# CRD.net
KiCad netlist of a schematic drawn in EAGLE
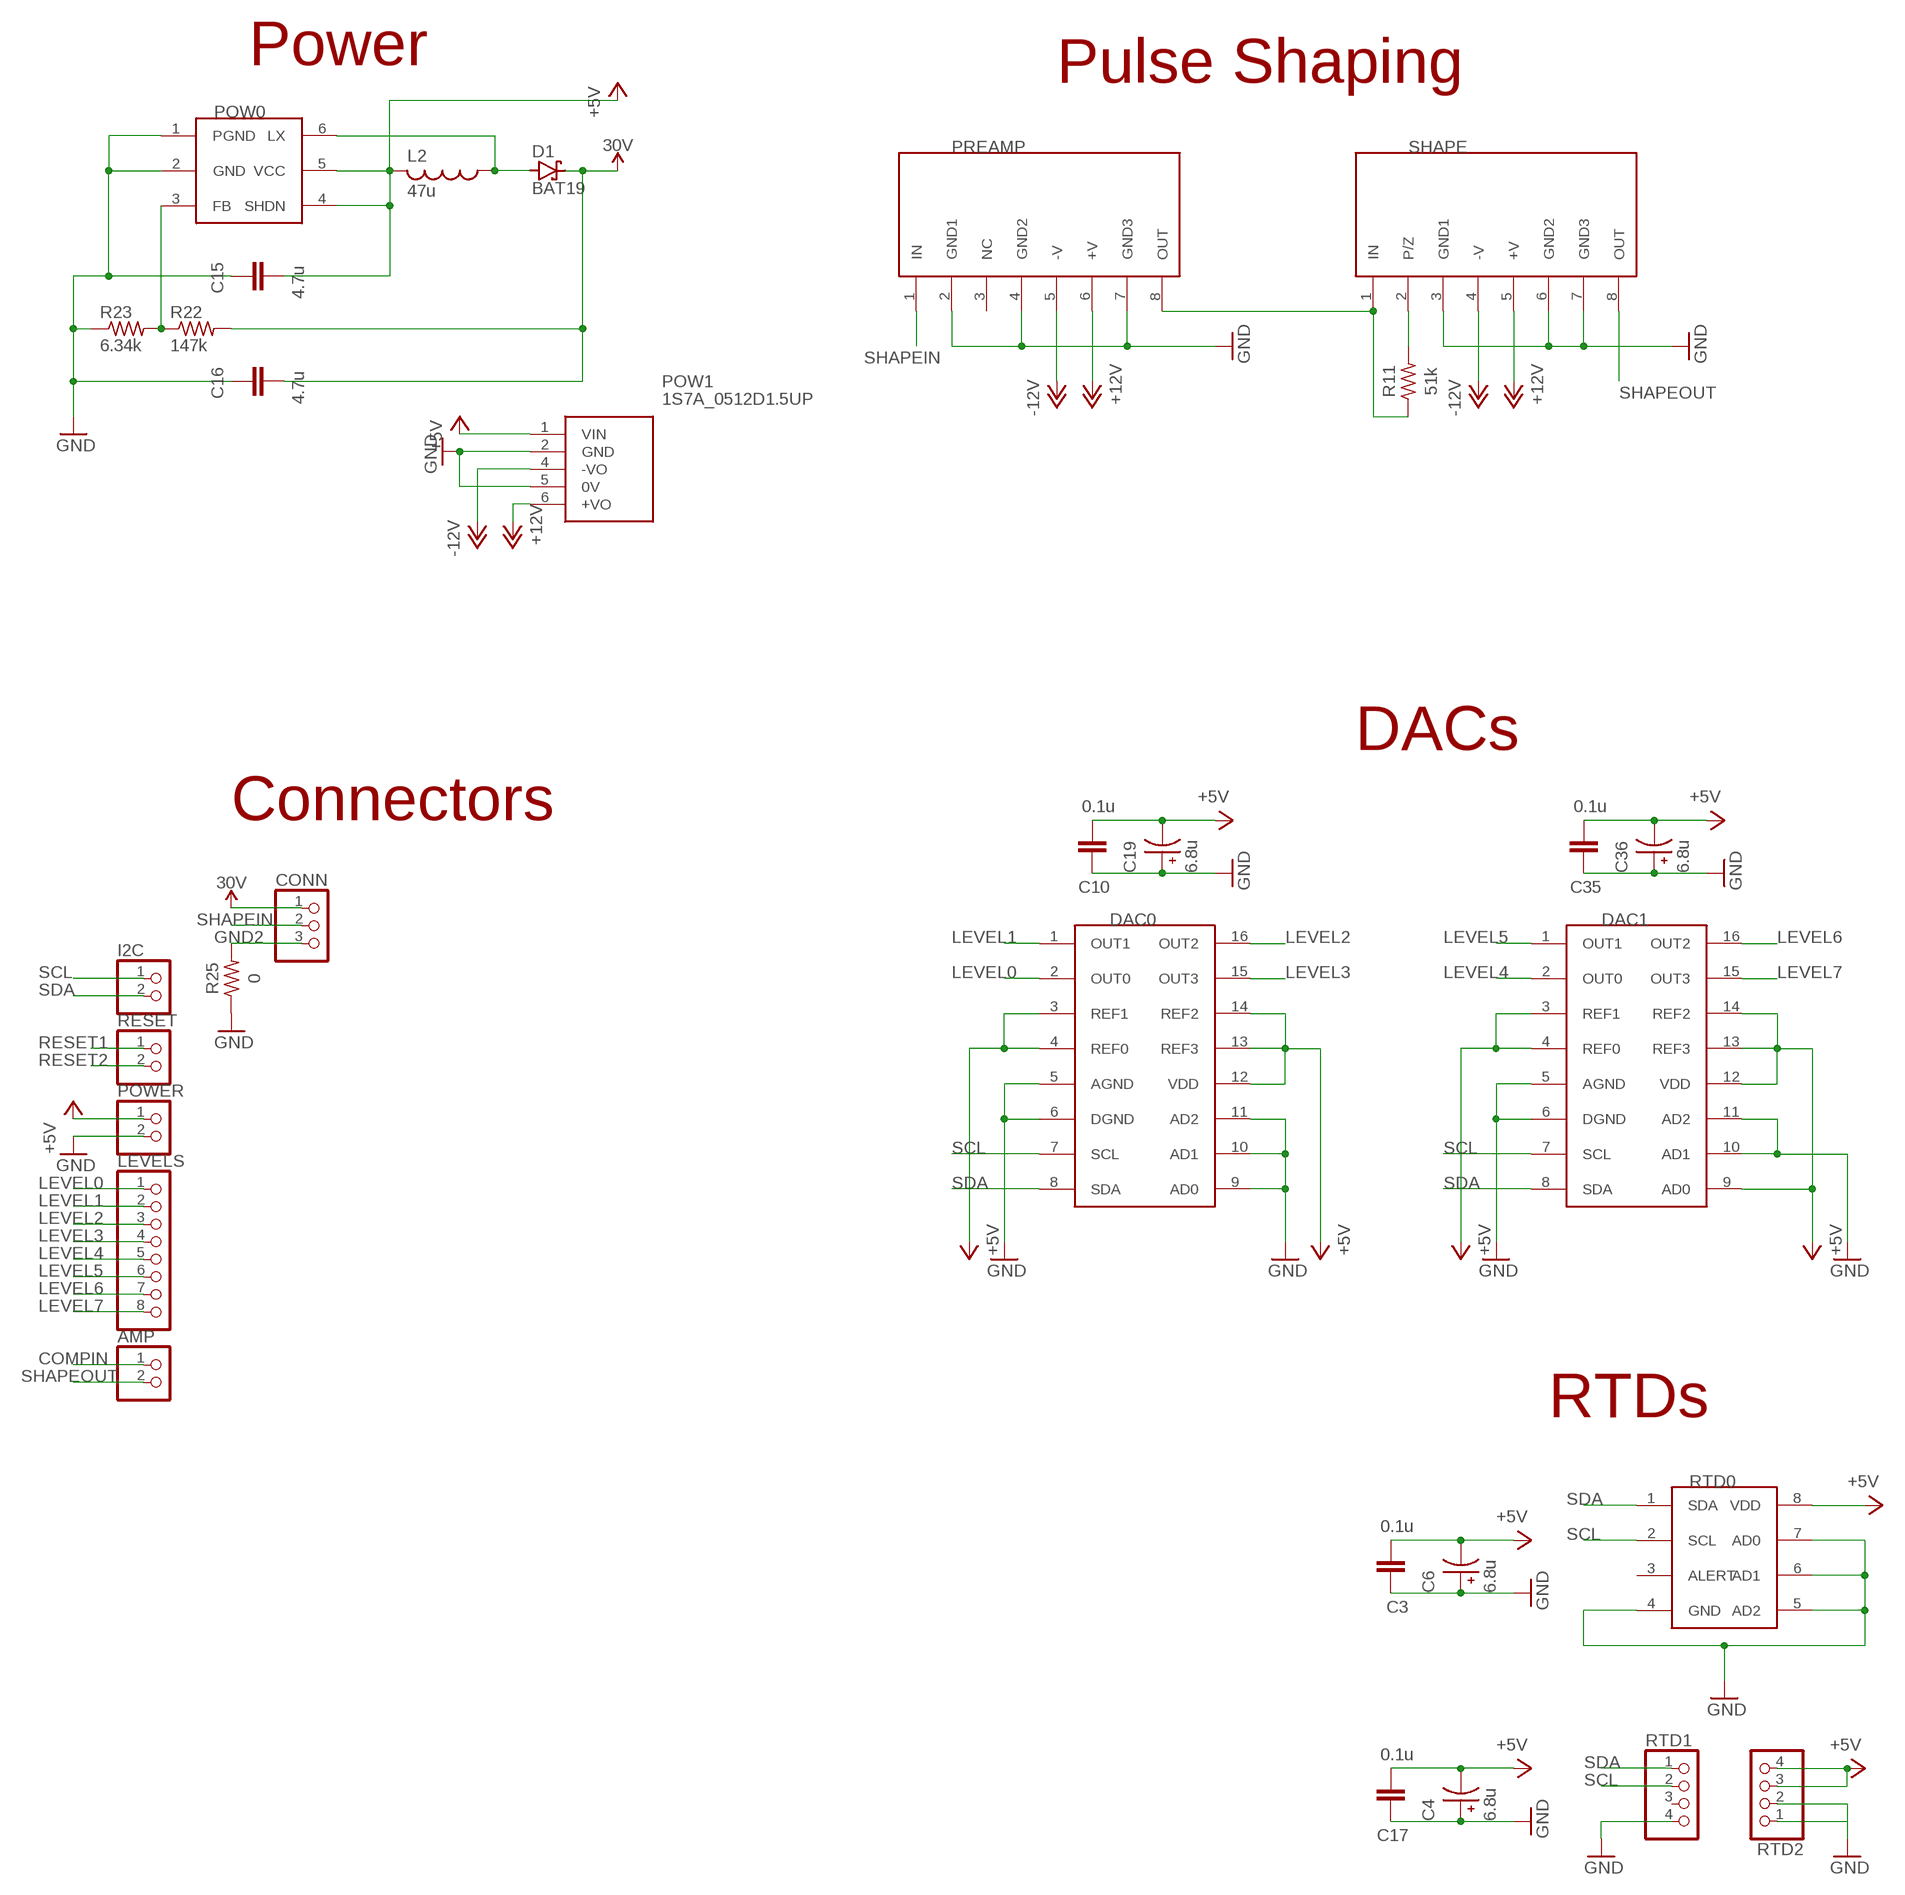
[diagram p0: schematic, sheet 1, part 1 of 2]
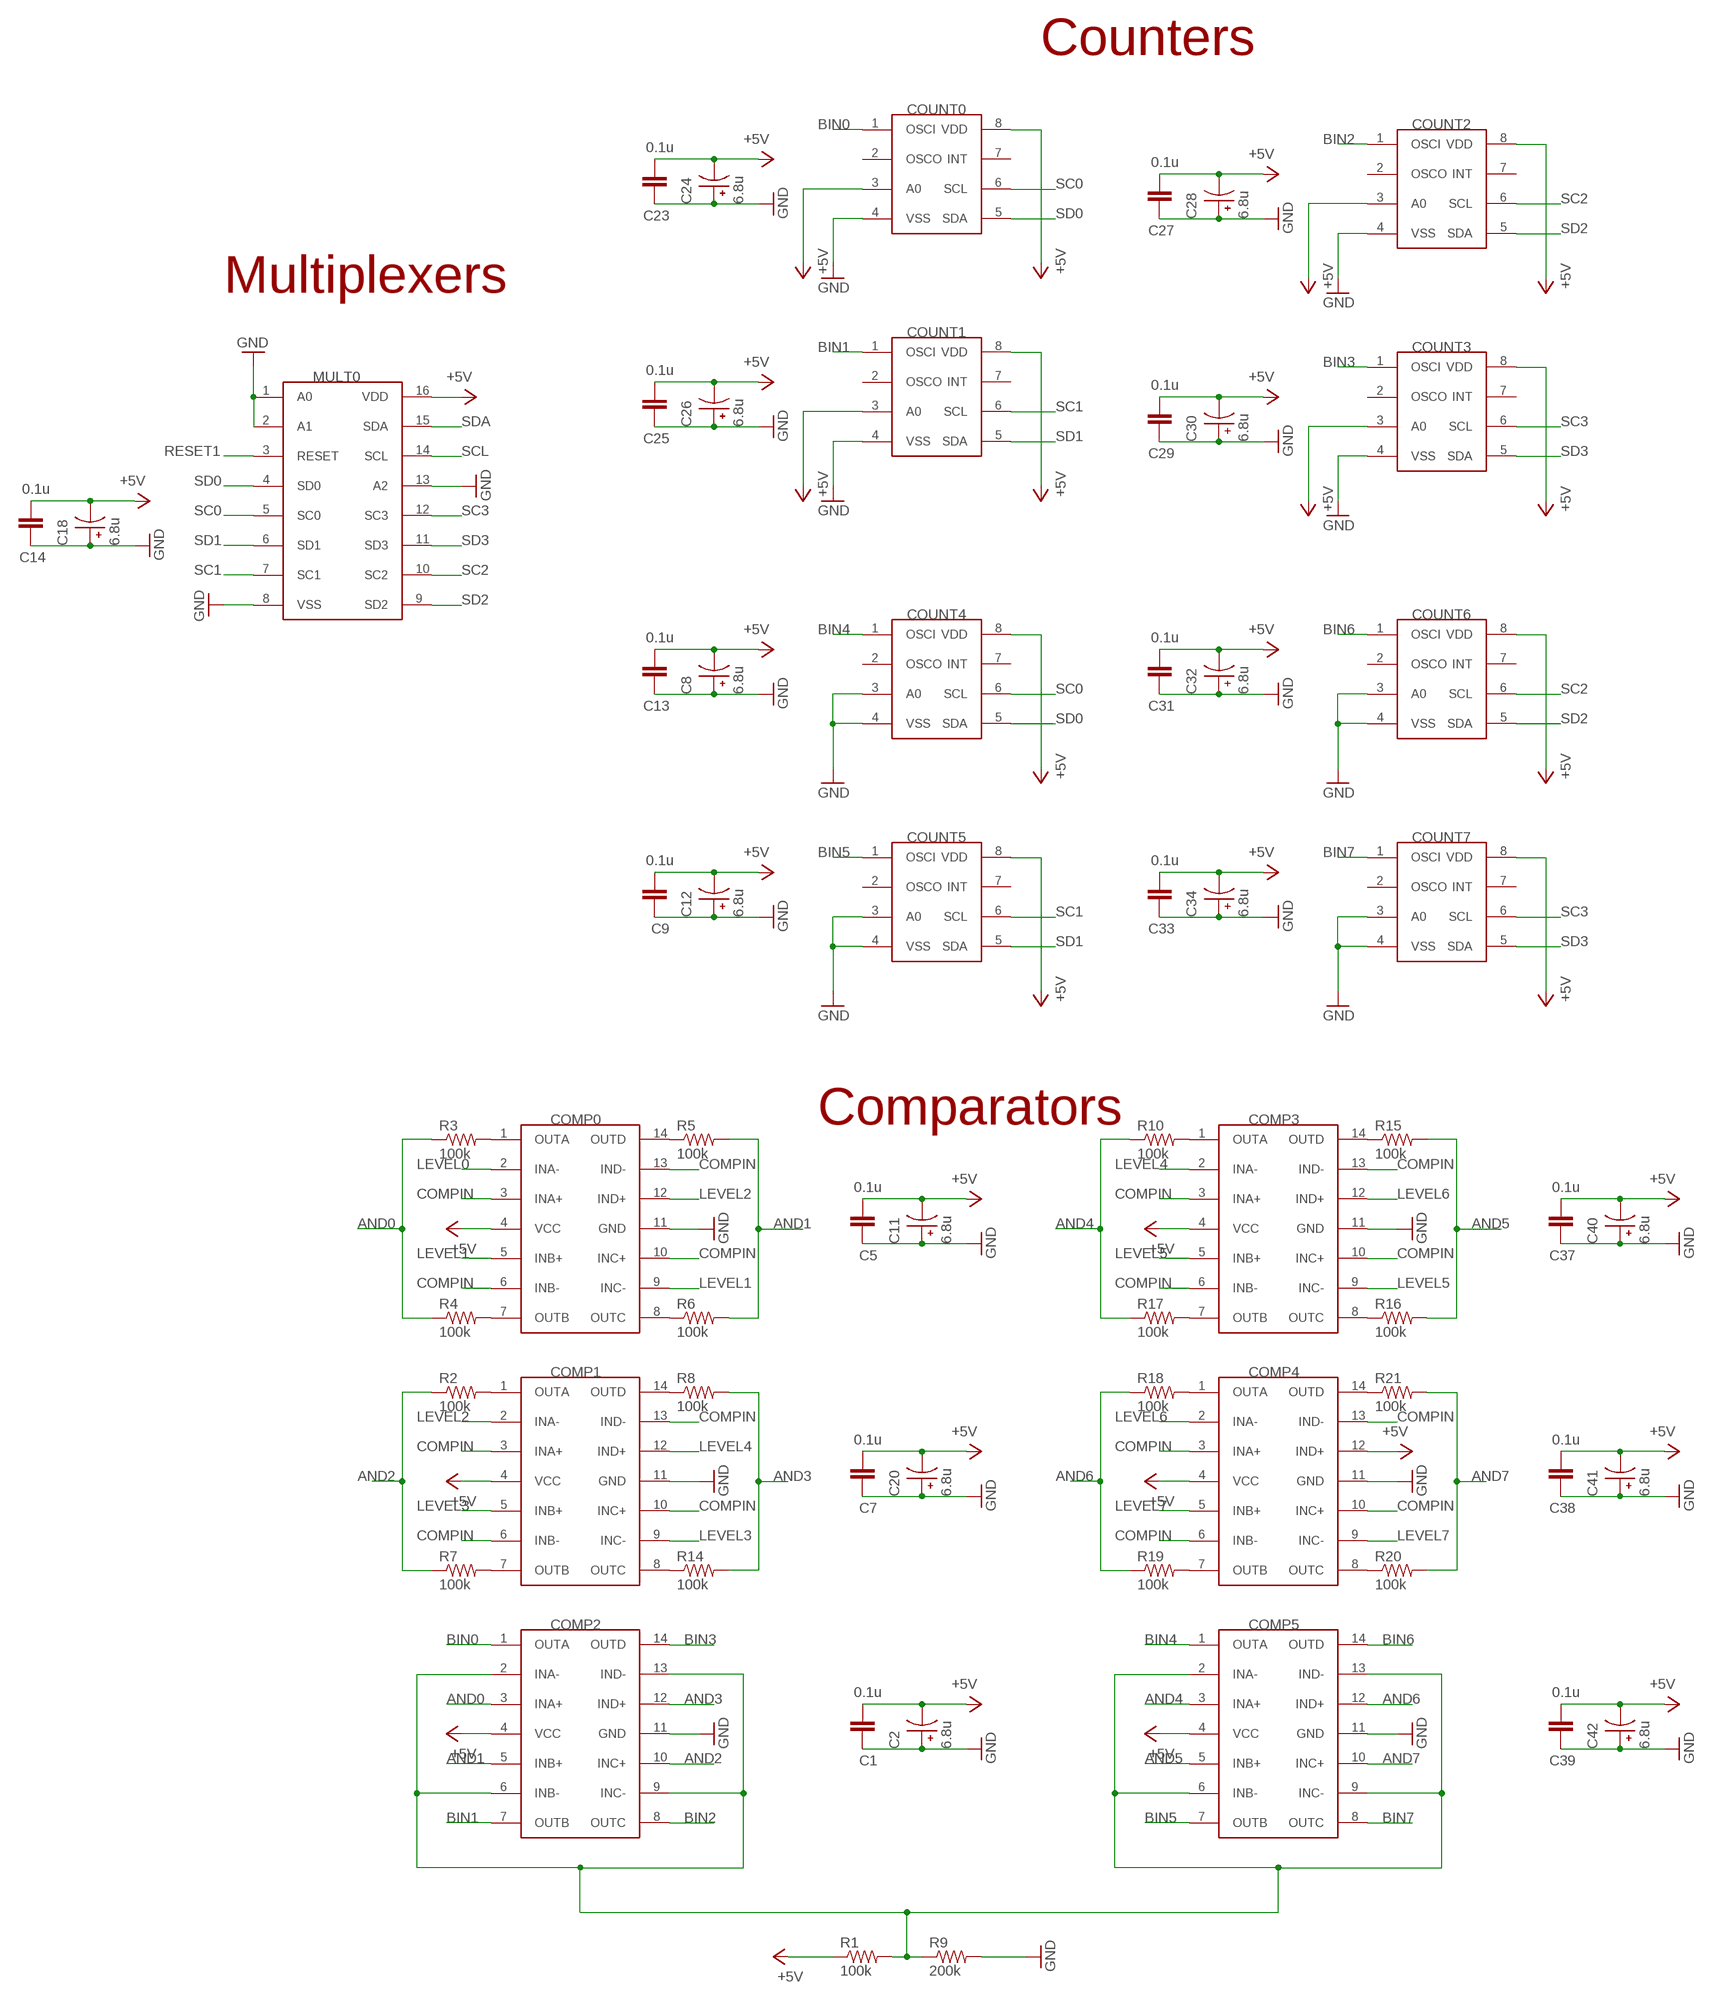
[diagram p1: schematic, sheet 1, part 2 of 2]

(export (version "E")
  (design (tool "Eeschema 10.0.6"))
  (components
    (comp (ref "AMP")
      (value "PINHD-1X2")
      (footprint "eagle-import:1X02")
      (libsource (lib "eagle-import") (part "PINHD-1X2"))
    )
    (comp (ref "C1")
      (value "0.1u")
      (footprint "eagle-import:CAP_1206")
      (fields
        (field (name "DIGIKEY_PART_NUMBER") "GRM31CR60J107ME39L")
        (field (name "MANUFACTURER") "Murata Electronics North America")
        (field (name "CREATED_BY") "PCBLayout.com")
      )
      (libsource (lib "eagle-import") (part "GRM31CR60J107ME39L"))
    )
    (comp (ref "C2")
      (value "6.8u")
      (footprint "eagle-import:CAPPRD150W45D400H700")
      (fields
        (field (name "DIGI-KEY_PART_NUMBER") "P14493-ND")
        (field (name "MF") "Panasonic")
        (field (name "MP") "EEAGA1V6R8")
      )
      (libsource (lib "eagle-import") (part "EEAGA1V6R8"))
    )
    (comp (ref "C3")
      (value "0.1u")
      (footprint "eagle-import:CAP_1206")
      (fields
        (field (name "DIGIKEY_PART_NUMBER") "GRM31CR60J107ME39L")
        (field (name "MANUFACTURER") "Murata Electronics North America")
        (field (name "CREATED_BY") "PCBLayout.com")
      )
      (libsource (lib "eagle-import") (part "GRM31CR60J107ME39L"))
    )
    (comp (ref "C4")
      (value "6.8u")
      (footprint "eagle-import:CAPPRD150W45D400H700")
      (fields
        (field (name "DIGI-KEY_PART_NUMBER") "P14493-ND")
        (field (name "MF") "Panasonic")
        (field (name "MP") "EEAGA1V6R8")
      )
      (libsource (lib "eagle-import") (part "EEAGA1V6R8"))
    )
    (comp (ref "C5")
      (value "0.1u")
      (footprint "eagle-import:CAP_1206")
      (fields
        (field (name "DIGIKEY_PART_NUMBER") "GRM31CR60J107ME39L")
        (field (name "MANUFACTURER") "Murata Electronics North America")
        (field (name "CREATED_BY") "PCBLayout.com")
      )
      (libsource (lib "eagle-import") (part "GRM31CR60J107ME39L"))
    )
    (comp (ref "C6")
      (value "6.8u")
      (footprint "eagle-import:CAPPRD150W45D400H700")
      (fields
        (field (name "DIGI-KEY_PART_NUMBER") "P14493-ND")
        (field (name "MF") "Panasonic")
        (field (name "MP") "EEAGA1V6R8")
      )
      (libsource (lib "eagle-import") (part "EEAGA1V6R8"))
    )
    (comp (ref "C7")
      (value "0.1u")
      (footprint "eagle-import:CAP_1206")
      (fields
        (field (name "DIGIKEY_PART_NUMBER") "GRM31CR60J107ME39L")
        (field (name "MANUFACTURER") "Murata Electronics North America")
        (field (name "CREATED_BY") "PCBLayout.com")
      )
      (libsource (lib "eagle-import") (part "GRM31CR60J107ME39L"))
    )
    (comp (ref "C8")
      (value "6.8u")
      (footprint "eagle-import:CAPPRD150W45D400H700")
      (fields
        (field (name "DIGI-KEY_PART_NUMBER") "P14493-ND")
        (field (name "MF") "Panasonic")
        (field (name "MP") "EEAGA1V6R8")
      )
      (libsource (lib "eagle-import") (part "EEAGA1V6R8"))
    )
    (comp (ref "C9")
      (value "0.1u")
      (footprint "eagle-import:CAP_1206")
      (fields
        (field (name "DIGIKEY_PART_NUMBER") "GRM31CR60J107ME39L")
        (field (name "MANUFACTURER") "Murata Electronics North America")
        (field (name "CREATED_BY") "PCBLayout.com")
      )
      (libsource (lib "eagle-import") (part "GRM31CR60J107ME39L"))
    )
    (comp (ref "C10")
      (value "0.1u")
      (footprint "eagle-import:CAP_1206")
      (fields
        (field (name "DIGIKEY_PART_NUMBER") "GRM31CR60J107ME39L")
        (field (name "MANUFACTURER") "Murata Electronics North America")
        (field (name "CREATED_BY") "PCBLayout.com")
      )
      (libsource (lib "eagle-import") (part "GRM31CR60J107ME39L"))
    )
    (comp (ref "C11")
      (value "6.8u")
      (footprint "eagle-import:CAPPRD150W45D400H700")
      (fields
        (field (name "DIGI-KEY_PART_NUMBER") "P14493-ND")
        (field (name "MF") "Panasonic")
        (field (name "MP") "EEAGA1V6R8")
      )
      (libsource (lib "eagle-import") (part "EEAGA1V6R8"))
    )
    (comp (ref "C12")
      (value "6.8u")
      (footprint "eagle-import:CAPPRD150W45D400H700")
      (fields
        (field (name "DIGI-KEY_PART_NUMBER") "P14493-ND")
        (field (name "MF") "Panasonic")
        (field (name "MP") "EEAGA1V6R8")
      )
      (libsource (lib "eagle-import") (part "EEAGA1V6R8"))
    )
    (comp (ref "C13")
      (value "0.1u")
      (footprint "eagle-import:CAP_1206")
      (fields
        (field (name "DIGIKEY_PART_NUMBER") "GRM31CR60J107ME39L")
        (field (name "MANUFACTURER") "Murata Electronics North America")
        (field (name "CREATED_BY") "PCBLayout.com")
      )
      (libsource (lib "eagle-import") (part "GRM31CR60J107ME39L"))
    )
    (comp (ref "C14")
      (value "0.1u")
      (footprint "eagle-import:CAP_1206")
      (fields
        (field (name "DIGIKEY_PART_NUMBER") "GRM31CR60J107ME39L")
        (field (name "MANUFACTURER") "Murata Electronics North America")
        (field (name "CREATED_BY") "PCBLayout.com")
      )
      (libsource (lib "eagle-import") (part "GRM31CR60J107ME39L"))
    )
    (comp (ref "C15")
      (value "4.7u")
      (footprint "eagle-import:CAP_1206")
      (fields
        (field (name "DIGIKEY_PART_NUMBER") "GRM31CR60J107ME39L")
        (field (name "MANUFACTURER") "Murata Electronics North America")
        (field (name "CREATED_BY") "PCBLayout.com")
      )
      (libsource (lib "eagle-import") (part "GRM31CR60J107ME39L"))
    )
    (comp (ref "C16")
      (value "4.7u")
      (footprint "eagle-import:CAP_1206")
      (fields
        (field (name "DIGIKEY_PART_NUMBER") "GRM31CR60J107ME39L")
        (field (name "MANUFACTURER") "Murata Electronics North America")
        (field (name "CREATED_BY") "PCBLayout.com")
      )
      (libsource (lib "eagle-import") (part "GRM31CR60J107ME39L"))
    )
    (comp (ref "C17")
      (value "0.1u")
      (footprint "eagle-import:CAP_1206")
      (fields
        (field (name "DIGIKEY_PART_NUMBER") "GRM31CR60J107ME39L")
        (field (name "MANUFACTURER") "Murata Electronics North America")
        (field (name "CREATED_BY") "PCBLayout.com")
      )
      (libsource (lib "eagle-import") (part "GRM31CR60J107ME39L"))
    )
    (comp (ref "C18")
      (value "6.8u")
      (footprint "eagle-import:CAPPRD150W45D400H700")
      (fields
        (field (name "DIGI-KEY_PART_NUMBER") "P14493-ND")
        (field (name "MF") "Panasonic")
        (field (name "MP") "EEAGA1V6R8")
      )
      (libsource (lib "eagle-import") (part "EEAGA1V6R8"))
    )
    (comp (ref "C19")
      (value "6.8u")
      (footprint "eagle-import:CAPPRD150W45D400H700")
      (fields
        (field (name "DIGI-KEY_PART_NUMBER") "P14493-ND")
        (field (name "MF") "Panasonic")
        (field (name "MP") "EEAGA1V6R8")
      )
      (libsource (lib "eagle-import") (part "EEAGA1V6R8"))
    )
    (comp (ref "C20")
      (value "6.8u")
      (footprint "eagle-import:CAPPRD150W45D400H700")
      (fields
        (field (name "DIGI-KEY_PART_NUMBER") "P14493-ND")
        (field (name "MF") "Panasonic")
        (field (name "MP") "EEAGA1V6R8")
      )
      (libsource (lib "eagle-import") (part "EEAGA1V6R8"))
    )
    (comp (ref "C23")
      (value "0.1u")
      (footprint "eagle-import:CAP_1206")
      (fields
        (field (name "DIGIKEY_PART_NUMBER") "GRM31CR60J107ME39L")
        (field (name "MANUFACTURER") "Murata Electronics North America")
        (field (name "CREATED_BY") "PCBLayout.com")
      )
      (libsource (lib "eagle-import") (part "GRM31CR60J107ME39L"))
    )
    (comp (ref "C24")
      (value "6.8u")
      (footprint "eagle-import:CAPPRD150W45D400H700")
      (fields
        (field (name "DIGI-KEY_PART_NUMBER") "P14493-ND")
        (field (name "MF") "Panasonic")
        (field (name "MP") "EEAGA1V6R8")
      )
      (libsource (lib "eagle-import") (part "EEAGA1V6R8"))
    )
    (comp (ref "C25")
      (value "0.1u")
      (footprint "eagle-import:CAP_1206")
      (fields
        (field (name "DIGIKEY_PART_NUMBER") "GRM31CR60J107ME39L")
        (field (name "MANUFACTURER") "Murata Electronics North America")
        (field (name "CREATED_BY") "PCBLayout.com")
      )
      (libsource (lib "eagle-import") (part "GRM31CR60J107ME39L"))
    )
    (comp (ref "C26")
      (value "6.8u")
      (footprint "eagle-import:CAPPRD150W45D400H700")
      (fields
        (field (name "DIGI-KEY_PART_NUMBER") "P14493-ND")
        (field (name "MF") "Panasonic")
        (field (name "MP") "EEAGA1V6R8")
      )
      (libsource (lib "eagle-import") (part "EEAGA1V6R8"))
    )
    (comp (ref "C27")
      (value "0.1u")
      (footprint "eagle-import:CAP_1206")
      (fields
        (field (name "DIGIKEY_PART_NUMBER") "GRM31CR60J107ME39L")
        (field (name "MANUFACTURER") "Murata Electronics North America")
        (field (name "CREATED_BY") "PCBLayout.com")
      )
      (libsource (lib "eagle-import") (part "GRM31CR60J107ME39L"))
    )
    (comp (ref "C28")
      (value "6.8u")
      (footprint "eagle-import:CAPPRD150W45D400H700")
      (fields
        (field (name "DIGI-KEY_PART_NUMBER") "P14493-ND")
        (field (name "MF") "Panasonic")
        (field (name "MP") "EEAGA1V6R8")
      )
      (libsource (lib "eagle-import") (part "EEAGA1V6R8"))
    )
    (comp (ref "C29")
      (value "0.1u")
      (footprint "eagle-import:CAP_1206")
      (fields
        (field (name "DIGIKEY_PART_NUMBER") "GRM31CR60J107ME39L")
        (field (name "MANUFACTURER") "Murata Electronics North America")
        (field (name "CREATED_BY") "PCBLayout.com")
      )
      (libsource (lib "eagle-import") (part "GRM31CR60J107ME39L"))
    )
    (comp (ref "C30")
      (value "6.8u")
      (footprint "eagle-import:CAPPRD150W45D400H700")
      (fields
        (field (name "DIGI-KEY_PART_NUMBER") "P14493-ND")
        (field (name "MF") "Panasonic")
        (field (name "MP") "EEAGA1V6R8")
      )
      (libsource (lib "eagle-import") (part "EEAGA1V6R8"))
    )
    (comp (ref "C31")
      (value "0.1u")
      (footprint "eagle-import:CAP_1206")
      (fields
        (field (name "DIGIKEY_PART_NUMBER") "GRM31CR60J107ME39L")
        (field (name "MANUFACTURER") "Murata Electronics North America")
        (field (name "CREATED_BY") "PCBLayout.com")
      )
      (libsource (lib "eagle-import") (part "GRM31CR60J107ME39L"))
    )
    (comp (ref "C32")
      (value "6.8u")
      (footprint "eagle-import:CAPPRD150W45D400H700")
      (fields
        (field (name "DIGI-KEY_PART_NUMBER") "P14493-ND")
        (field (name "MF") "Panasonic")
        (field (name "MP") "EEAGA1V6R8")
      )
      (libsource (lib "eagle-import") (part "EEAGA1V6R8"))
    )
    (comp (ref "C33")
      (value "0.1u")
      (footprint "eagle-import:CAP_1206")
      (fields
        (field (name "DIGIKEY_PART_NUMBER") "GRM31CR60J107ME39L")
        (field (name "MANUFACTURER") "Murata Electronics North America")
        (field (name "CREATED_BY") "PCBLayout.com")
      )
      (libsource (lib "eagle-import") (part "GRM31CR60J107ME39L"))
    )
    (comp (ref "C34")
      (value "6.8u")
      (footprint "eagle-import:CAPPRD150W45D400H700")
      (fields
        (field (name "DIGI-KEY_PART_NUMBER") "P14493-ND")
        (field (name "MF") "Panasonic")
        (field (name "MP") "EEAGA1V6R8")
      )
      (libsource (lib "eagle-import") (part "EEAGA1V6R8"))
    )
    (comp (ref "C35")
      (value "0.1u")
      (footprint "eagle-import:CAP_1206")
      (fields
        (field (name "DIGIKEY_PART_NUMBER") "GRM31CR60J107ME39L")
        (field (name "MANUFACTURER") "Murata Electronics North America")
        (field (name "CREATED_BY") "PCBLayout.com")
      )
      (libsource (lib "eagle-import") (part "GRM31CR60J107ME39L"))
    )
    (comp (ref "C36")
      (value "6.8u")
      (footprint "eagle-import:CAPPRD150W45D400H700")
      (fields
        (field (name "DIGI-KEY_PART_NUMBER") "P14493-ND")
        (field (name "MF") "Panasonic")
        (field (name "MP") "EEAGA1V6R8")
      )
      (libsource (lib "eagle-import") (part "EEAGA1V6R8"))
    )
    (comp (ref "C37")
      (value "0.1u")
      (footprint "eagle-import:CAP_1206")
      (fields
        (field (name "DIGIKEY_PART_NUMBER") "GRM31CR60J107ME39L")
        (field (name "MANUFACTURER") "Murata Electronics North America")
        (field (name "CREATED_BY") "PCBLayout.com")
      )
      (libsource (lib "eagle-import") (part "GRM31CR60J107ME39L"))
    )
    (comp (ref "C38")
      (value "0.1u")
      (footprint "eagle-import:CAP_1206")
      (fields
        (field (name "DIGIKEY_PART_NUMBER") "GRM31CR60J107ME39L")
        (field (name "MANUFACTURER") "Murata Electronics North America")
        (field (name "CREATED_BY") "PCBLayout.com")
      )
      (libsource (lib "eagle-import") (part "GRM31CR60J107ME39L"))
    )
    (comp (ref "C39")
      (value "0.1u")
      (footprint "eagle-import:CAP_1206")
      (fields
        (field (name "DIGIKEY_PART_NUMBER") "GRM31CR60J107ME39L")
        (field (name "MANUFACTURER") "Murata Electronics North America")
        (field (name "CREATED_BY") "PCBLayout.com")
      )
      (libsource (lib "eagle-import") (part "GRM31CR60J107ME39L"))
    )
    (comp (ref "C40")
      (value "6.8u")
      (footprint "eagle-import:CAPPRD150W45D400H700")
      (fields
        (field (name "DIGI-KEY_PART_NUMBER") "P14493-ND")
        (field (name "MF") "Panasonic")
        (field (name "MP") "EEAGA1V6R8")
      )
      (libsource (lib "eagle-import") (part "EEAGA1V6R8"))
    )
    (comp (ref "C41")
      (value "6.8u")
      (footprint "eagle-import:CAPPRD150W45D400H700")
      (fields
        (field (name "DIGI-KEY_PART_NUMBER") "P14493-ND")
        (field (name "MF") "Panasonic")
        (field (name "MP") "EEAGA1V6R8")
      )
      (libsource (lib "eagle-import") (part "EEAGA1V6R8"))
    )
    (comp (ref "C42")
      (value "6.8u")
      (footprint "eagle-import:CAPPRD150W45D400H700")
      (fields
        (field (name "DIGI-KEY_PART_NUMBER") "P14493-ND")
        (field (name "MF") "Panasonic")
        (field (name "MP") "EEAGA1V6R8")
      )
      (libsource (lib "eagle-import") (part "EEAGA1V6R8"))
    )
    (comp (ref "COMP0")
      (value "MAX9108ESD+")
      (footprint "eagle-import:SOIC127P600X155-14N")
      (libsource (lib "eagle-import") (part "MAX9108ESD+"))
    )
    (comp (ref "COMP1")
      (value "MAX9108ESD+")
      (footprint "eagle-import:SOIC127P600X155-14N")
      (libsource (lib "eagle-import") (part "MAX9108ESD+"))
    )
    (comp (ref "COMP2")
      (value "MAX9108ESD+")
      (footprint "eagle-import:SOIC127P600X155-14N")
      (libsource (lib "eagle-import") (part "MAX9108ESD+"))
    )
    (comp (ref "COMP3")
      (value "MAX9108ESD+")
      (footprint "eagle-import:SOIC127P600X155-14N")
      (libsource (lib "eagle-import") (part "MAX9108ESD+"))
    )
    (comp (ref "COMP4")
      (value "MAX9108ESD+")
      (footprint "eagle-import:SOIC127P600X155-14N")
      (libsource (lib "eagle-import") (part "MAX9108ESD+"))
    )
    (comp (ref "COMP5")
      (value "MAX9108ESD+")
      (footprint "eagle-import:SOIC127P600X155-14N")
      (libsource (lib "eagle-import") (part "MAX9108ESD+"))
    )
    (comp (ref "CONN")
      (value "PINHD-1X3")
      (footprint "eagle-import:1X03")
      (libsource (lib "eagle-import") (part "PINHD-1X3"))
    )
    (comp (ref "COUNT0")
      (value "PCF8583")
      (footprint "eagle-import:SOIC127P1032X265-8N")
      (libsource (lib "eagle-import") (part "PCF8583"))
    )
    (comp (ref "COUNT1")
      (value "PCF8583")
      (footprint "eagle-import:SOIC127P1032X265-8N")
      (libsource (lib "eagle-import") (part "PCF8583"))
    )
    (comp (ref "COUNT2")
      (value "PCF8583")
      (footprint "eagle-import:SOIC127P1032X265-8N")
      (libsource (lib "eagle-import") (part "PCF8583"))
    )
    (comp (ref "COUNT3")
      (value "PCF8583")
      (footprint "eagle-import:SOIC127P1032X265-8N")
      (libsource (lib "eagle-import") (part "PCF8583"))
    )
    (comp (ref "COUNT4")
      (value "PCF8583")
      (footprint "eagle-import:SOIC127P1032X265-8N")
      (libsource (lib "eagle-import") (part "PCF8583"))
    )
    (comp (ref "COUNT5")
      (value "PCF8583")
      (footprint "eagle-import:SOIC127P1032X265-8N")
      (libsource (lib "eagle-import") (part "PCF8583"))
    )
    (comp (ref "COUNT6")
      (value "PCF8583")
      (footprint "eagle-import:SOIC127P1032X265-8N")
      (libsource (lib "eagle-import") (part "PCF8583"))
    )
    (comp (ref "COUNT7")
      (value "PCF8583")
      (footprint "eagle-import:SOIC127P1032X265-8N")
      (libsource (lib "eagle-import") (part "PCF8583"))
    )
    (comp (ref "D1")
      (value "BAT19")
      (footprint "eagle-import:DO35-10")
      (libsource (lib "eagle-import") (part "BAT19"))
    )
    (comp (ref "DAC0")
      (value "MAX520BEWE+")
      (footprint "eagle-import:SOIC127P1032X265-16N")
      (libsource (lib "eagle-import") (part "MAX520BEWE+"))
    )
    (comp (ref "DAC1")
      (value "MAX520BEWE+")
      (footprint "eagle-import:SOIC127P1032X265-16N")
      (libsource (lib "eagle-import") (part "MAX520BEWE+"))
    )
    (comp (ref "I2C")
      (value "PINHD-1X2")
      (footprint "eagle-import:1X02")
      (libsource (lib "eagle-import") (part "PINHD-1X2"))
    )
    (comp (ref "L2")
      (value "47u")
      (footprint "eagle-import:L1812")
      (libsource (lib "eagle-import") (part "L-USL1812"))
    )
    (comp (ref "LEVELS")
      (value "PINHD-1X8")
      (footprint "eagle-import:1X08")
      (libsource (lib "eagle-import") (part "PINHD-1X8"))
    )
    (comp (ref "MULT0")
      (value "PCA9546A")
      (footprint "eagle-import:SOIC127P600X175-16N")
      (libsource (lib "eagle-import") (part "PCA9546A"))
    )
    (comp (ref "POW0")
      (value "MAX5025")
      (footprint "eagle-import:SOT95P240X110-6N")
      (libsource (lib "eagle-import") (part "MAX5025"))
    )
    (comp (ref "POW1")
      (value "1S7A_0512D1.5UP")
      (footprint "eagle-import:1S7A_0505D15UP")
      (libsource (lib "eagle-import") (part "1S7A_0512D1.5UP"))
    )
    (comp (ref "POWER")
      (value "PINHD-1X2")
      (footprint "eagle-import:1X02")
      (libsource (lib "eagle-import") (part "PINHD-1X2"))
    )
    (comp (ref "PREAMP")
      (value "CR-113")
      (footprint "eagle-import:HDRV8W64P254_1X8_1016X508X838B")
      (libsource (lib "eagle-import") (part "CR-113"))
    )
    (comp (ref "R1")
      (value "100k")
      (footprint "eagle-import:RES_1206")
      (fields
        (field (name "DIGIKEY_PART_NUMBER") "P0.0ETR-ND")
        (field (name "MANUFACTURER") "Panasonic Electronic Components")
        (field (name "MPN") "ERJ-8GEY0R00V")
        (field (name "CREATED_BY") "PCBLayout.com")
      )
      (libsource (lib "eagle-import") (part "ERJ-8GEY0R00V"))
    )
    (comp (ref "R2")
      (value "100k")
      (footprint "eagle-import:RES_1206")
      (fields
        (field (name "DIGIKEY_PART_NUMBER") "P0.0ETR-ND")
        (field (name "MANUFACTURER") "Panasonic Electronic Components")
        (field (name "MPN") "ERJ-8GEY0R00V")
        (field (name "CREATED_BY") "PCBLayout.com")
      )
      (libsource (lib "eagle-import") (part "ERJ-8GEY0R00V"))
    )
    (comp (ref "R3")
      (value "100k")
      (footprint "eagle-import:RES_1206")
      (fields
        (field (name "DIGIKEY_PART_NUMBER") "P0.0ETR-ND")
        (field (name "MANUFACTURER") "Panasonic Electronic Components")
        (field (name "MPN") "ERJ-8GEY0R00V")
        (field (name "CREATED_BY") "PCBLayout.com")
      )
      (libsource (lib "eagle-import") (part "ERJ-8GEY0R00V"))
    )
    (comp (ref "R4")
      (value "100k")
      (footprint "eagle-import:RES_1206")
      (fields
        (field (name "DIGIKEY_PART_NUMBER") "P0.0ETR-ND")
        (field (name "MANUFACTURER") "Panasonic Electronic Components")
        (field (name "MPN") "ERJ-8GEY0R00V")
        (field (name "CREATED_BY") "PCBLayout.com")
      )
      (libsource (lib "eagle-import") (part "ERJ-8GEY0R00V"))
    )
    (comp (ref "R5")
      (value "100k")
      (footprint "eagle-import:RES_1206")
      (fields
        (field (name "DIGIKEY_PART_NUMBER") "P0.0ETR-ND")
        (field (name "MANUFACTURER") "Panasonic Electronic Components")
        (field (name "MPN") "ERJ-8GEY0R00V")
        (field (name "CREATED_BY") "PCBLayout.com")
      )
      (libsource (lib "eagle-import") (part "ERJ-8GEY0R00V"))
    )
    (comp (ref "R6")
      (value "100k")
      (footprint "eagle-import:RES_1206")
      (fields
        (field (name "DIGIKEY_PART_NUMBER") "P0.0ETR-ND")
        (field (name "MANUFACTURER") "Panasonic Electronic Components")
        (field (name "MPN") "ERJ-8GEY0R00V")
        (field (name "CREATED_BY") "PCBLayout.com")
      )
      (libsource (lib "eagle-import") (part "ERJ-8GEY0R00V"))
    )
    (comp (ref "R7")
      (value "100k")
      (footprint "eagle-import:RES_1206")
      (fields
        (field (name "DIGIKEY_PART_NUMBER") "P0.0ETR-ND")
        (field (name "MANUFACTURER") "Panasonic Electronic Components")
        (field (name "MPN") "ERJ-8GEY0R00V")
        (field (name "CREATED_BY") "PCBLayout.com")
      )
      (libsource (lib "eagle-import") (part "ERJ-8GEY0R00V"))
    )
    (comp (ref "R8")
      (value "100k")
      (footprint "eagle-import:RES_1206")
      (fields
        (field (name "DIGIKEY_PART_NUMBER") "P0.0ETR-ND")
        (field (name "MANUFACTURER") "Panasonic Electronic Components")
        (field (name "MPN") "ERJ-8GEY0R00V")
        (field (name "CREATED_BY") "PCBLayout.com")
      )
      (libsource (lib "eagle-import") (part "ERJ-8GEY0R00V"))
    )
    (comp (ref "R9")
      (value "200k")
      (footprint "eagle-import:RES_1206")
      (fields
        (field (name "DIGIKEY_PART_NUMBER") "P0.0ETR-ND")
        (field (name "MANUFACTURER") "Panasonic Electronic Components")
        (field (name "MPN") "ERJ-8GEY0R00V")
        (field (name "CREATED_BY") "PCBLayout.com")
      )
      (libsource (lib "eagle-import") (part "ERJ-8GEY0R00V"))
    )
    (comp (ref "R10")
      (value "100k")
      (footprint "eagle-import:RES_1206")
      (fields
        (field (name "DIGIKEY_PART_NUMBER") "P0.0ETR-ND")
        (field (name "MANUFACTURER") "Panasonic Electronic Components")
        (field (name "MPN") "ERJ-8GEY0R00V")
        (field (name "CREATED_BY") "PCBLayout.com")
      )
      (libsource (lib "eagle-import") (part "ERJ-8GEY0R00V"))
    )
    (comp (ref "R11")
      (value "51k")
      (footprint "eagle-import:RESAD1176W63L850D250B")
      (libsource (lib "eagle-import") (part "R-USAXIAL-11.7MM-PITCH_"))
    )
    (comp (ref "R14")
      (value "100k")
      (footprint "eagle-import:RES_1206")
      (fields
        (field (name "DIGIKEY_PART_NUMBER") "P0.0ETR-ND")
        (field (name "MANUFACTURER") "Panasonic Electronic Components")
        (field (name "MPN") "ERJ-8GEY0R00V")
        (field (name "CREATED_BY") "PCBLayout.com")
      )
      (libsource (lib "eagle-import") (part "ERJ-8GEY0R00V"))
    )
    (comp (ref "R15")
      (value "100k")
      (footprint "eagle-import:RES_1206")
      (fields
        (field (name "DIGIKEY_PART_NUMBER") "P0.0ETR-ND")
        (field (name "MANUFACTURER") "Panasonic Electronic Components")
        (field (name "MPN") "ERJ-8GEY0R00V")
        (field (name "CREATED_BY") "PCBLayout.com")
      )
      (libsource (lib "eagle-import") (part "ERJ-8GEY0R00V"))
    )
    (comp (ref "R16")
      (value "100k")
      (footprint "eagle-import:RES_1206")
      (fields
        (field (name "DIGIKEY_PART_NUMBER") "P0.0ETR-ND")
        (field (name "MANUFACTURER") "Panasonic Electronic Components")
        (field (name "MPN") "ERJ-8GEY0R00V")
        (field (name "CREATED_BY") "PCBLayout.com")
      )
      (libsource (lib "eagle-import") (part "ERJ-8GEY0R00V"))
    )
    (comp (ref "R17")
      (value "100k")
      (footprint "eagle-import:RES_1206")
      (fields
        (field (name "DIGIKEY_PART_NUMBER") "P0.0ETR-ND")
        (field (name "MANUFACTURER") "Panasonic Electronic Components")
        (field (name "MPN") "ERJ-8GEY0R00V")
        (field (name "CREATED_BY") "PCBLayout.com")
      )
      (libsource (lib "eagle-import") (part "ERJ-8GEY0R00V"))
    )
    (comp (ref "R18")
      (value "100k")
      (footprint "eagle-import:RES_1206")
      (fields
        (field (name "DIGIKEY_PART_NUMBER") "P0.0ETR-ND")
        (field (name "MANUFACTURER") "Panasonic Electronic Components")
        (field (name "MPN") "ERJ-8GEY0R00V")
        (field (name "CREATED_BY") "PCBLayout.com")
      )
      (libsource (lib "eagle-import") (part "ERJ-8GEY0R00V"))
    )
    (comp (ref "R19")
      (value "100k")
      (footprint "eagle-import:RES_1206")
      (fields
        (field (name "DIGIKEY_PART_NUMBER") "P0.0ETR-ND")
        (field (name "MANUFACTURER") "Panasonic Electronic Components")
        (field (name "MPN") "ERJ-8GEY0R00V")
        (field (name "CREATED_BY") "PCBLayout.com")
      )
      (libsource (lib "eagle-import") (part "ERJ-8GEY0R00V"))
    )
    (comp (ref "R20")
      (value "100k")
      (footprint "eagle-import:RES_1206")
      (fields
        (field (name "DIGIKEY_PART_NUMBER") "P0.0ETR-ND")
        (field (name "MANUFACTURER") "Panasonic Electronic Components")
        (field (name "MPN") "ERJ-8GEY0R00V")
        (field (name "CREATED_BY") "PCBLayout.com")
      )
      (libsource (lib "eagle-import") (part "ERJ-8GEY0R00V"))
    )
    (comp (ref "R21")
      (value "100k")
      (footprint "eagle-import:RES_1206")
      (fields
        (field (name "DIGIKEY_PART_NUMBER") "P0.0ETR-ND")
        (field (name "MANUFACTURER") "Panasonic Electronic Components")
        (field (name "MPN") "ERJ-8GEY0R00V")
        (field (name "CREATED_BY") "PCBLayout.com")
      )
      (libsource (lib "eagle-import") (part "ERJ-8GEY0R00V"))
    )
    (comp (ref "R22")
      (value "147k")
      (footprint "eagle-import:RES_1206")
      (fields
        (field (name "DIGIKEY_PART_NUMBER") "P0.0ETR-ND")
        (field (name "MANUFACTURER") "Panasonic Electronic Components")
        (field (name "MPN") "ERJ-8GEY0R00V")
        (field (name "CREATED_BY") "PCBLayout.com")
      )
      (libsource (lib "eagle-import") (part "ERJ-8GEY0R00V"))
    )
    (comp (ref "R23")
      (value "6.34k")
      (footprint "eagle-import:RES_1206")
      (fields
        (field (name "DIGIKEY_PART_NUMBER") "P0.0ETR-ND")
        (field (name "MANUFACTURER") "Panasonic Electronic Components")
        (field (name "MPN") "ERJ-8GEY0R00V")
        (field (name "CREATED_BY") "PCBLayout.com")
      )
      (libsource (lib "eagle-import") (part "ERJ-8GEY0R00V"))
    )
    (comp (ref "R25")
      (value "0")
      (footprint "eagle-import:RESAD724W46L381D178B")
      (libsource (lib "eagle-import") (part "R-USAXIAL-7.2MM-PITCH_"))
    )
    (comp (ref "RESET")
      (value "PINHD-1X2")
      (footprint "eagle-import:1X02")
      (libsource (lib "eagle-import") (part "PINHD-1X2"))
    )
    (comp (ref "RTD0")
      (value "NCT175DMR2G")
      (footprint "eagle-import:SOP65P490X110-8N")
      (libsource (lib "eagle-import") (part "NCT175DMR2G"))
    )
    (comp (ref "RTD1")
      (value "PINHD-1X4")
      (footprint "eagle-import:1X04")
      (libsource (lib "eagle-import") (part "PINHD-1X4"))
    )
    (comp (ref "RTD2")
      (value "PINHD-1X4")
      (footprint "eagle-import:1X04")
      (libsource (lib "eagle-import") (part "PINHD-1X4"))
    )
    (comp (ref "SHAPE")
      (value "CR-200")
      (footprint "eagle-import:HDRV8W64P254_1X8_1016X508X838B")
      (libsource (lib "eagle-import") (part "CR-200"))
    )
  )
  (nets
    (net (code "1") (name "+5V") (class "Default")
      (node (ref "C1") (pin "2") (pinfunction "2_2") (pintype "passive"))
      (node (ref "C10") (pin "2") (pinfunction "2_2") (pintype "passive"))
      (node (ref "C11") (pin "N") (pinfunction "N_N") (pintype "passive"))
      (node (ref "C12") (pin "N") (pinfunction "N_N") (pintype "passive"))
      (node (ref "C13") (pin "2") (pinfunction "2_2") (pintype "passive"))
      (node (ref "C14") (pin "2") (pinfunction "2_2") (pintype "passive"))
      (node (ref "C15") (pin "2") (pinfunction "2_2") (pintype "passive"))
      (node (ref "C17") (pin "2") (pinfunction "2_2") (pintype "passive"))
      (node (ref "C18") (pin "N") (pinfunction "N_N") (pintype "passive"))
      (node (ref "C19") (pin "N") (pinfunction "N_N") (pintype "passive"))
      (node (ref "C2") (pin "N") (pinfunction "N_N") (pintype "passive"))
      (node (ref "C20") (pin "N") (pinfunction "N_N") (pintype "passive"))
      (node (ref "C23") (pin "2") (pinfunction "2_2") (pintype "passive"))
      (node (ref "C24") (pin "N") (pinfunction "N_N") (pintype "passive"))
      (node (ref "C25") (pin "2") (pinfunction "2_2") (pintype "passive"))
      (node (ref "C26") (pin "N") (pinfunction "N_N") (pintype "passive"))
      (node (ref "C27") (pin "2") (pinfunction "2_2") (pintype "passive"))
      (node (ref "C28") (pin "N") (pinfunction "N_N") (pintype "passive"))
      (node (ref "C29") (pin "2") (pinfunction "2_2") (pintype "passive"))
      (node (ref "C3") (pin "2") (pinfunction "2_2") (pintype "passive"))
      (node (ref "C30") (pin "N") (pinfunction "N_N") (pintype "passive"))
      (node (ref "C31") (pin "2") (pinfunction "2_2") (pintype "passive"))
      (node (ref "C32") (pin "N") (pinfunction "N_N") (pintype "passive"))
      (node (ref "C33") (pin "2") (pinfunction "2_2") (pintype "passive"))
      (node (ref "C34") (pin "N") (pinfunction "N_N") (pintype "passive"))
      (node (ref "C35") (pin "2") (pinfunction "2_2") (pintype "passive"))
      (node (ref "C36") (pin "N") (pinfunction "N_N") (pintype "passive"))
      (node (ref "C37") (pin "2") (pinfunction "2_2") (pintype "passive"))
      (node (ref "C38") (pin "2") (pinfunction "2_2") (pintype "passive"))
      (node (ref "C39") (pin "2") (pinfunction "2_2") (pintype "passive"))
      (node (ref "C4") (pin "N") (pinfunction "N_N") (pintype "passive"))
      (node (ref "C40") (pin "N") (pinfunction "N_N") (pintype "passive"))
      (node (ref "C41") (pin "N") (pinfunction "N_N") (pintype "passive"))
      (node (ref "C42") (pin "N") (pinfunction "N_N") (pintype "passive"))
      (node (ref "C5") (pin "2") (pinfunction "2_2") (pintype "passive"))
      (node (ref "C6") (pin "N") (pinfunction "N_N") (pintype "passive"))
      (node (ref "C7") (pin "2") (pinfunction "2_2") (pintype "passive"))
      (node (ref "C8") (pin "N") (pinfunction "N_N") (pintype "passive"))
      (node (ref "C9") (pin "2") (pinfunction "2_2") (pintype "passive"))
      (node (ref "COMP0") (pin "4") (pinfunction "VCC_4") (pintype "bidirectional"))
      (node (ref "COMP1") (pin "4") (pinfunction "VCC_4") (pintype "bidirectional"))
      (node (ref "COMP2") (pin "4") (pinfunction "VCC_4") (pintype "bidirectional"))
      (node (ref "COMP3") (pin "4") (pinfunction "VCC_4") (pintype "bidirectional"))
      (node (ref "COMP4") (pin "12") (pinfunction "IND+_12") (pintype "bidirectional"))
      (node (ref "COMP4") (pin "4") (pinfunction "VCC_4") (pintype "bidirectional"))
      (node (ref "COMP5") (pin "4") (pinfunction "VCC_4") (pintype "bidirectional"))
      (node (ref "COUNT0") (pin "3") (pinfunction "A0_3") (pintype "bidirectional"))
      (node (ref "COUNT0") (pin "8") (pinfunction "VDD_8") (pintype "bidirectional"))
      (node (ref "COUNT1") (pin "3") (pinfunction "A0_3") (pintype "bidirectional"))
      (node (ref "COUNT1") (pin "8") (pinfunction "VDD_8") (pintype "bidirectional"))
      (node (ref "COUNT2") (pin "3") (pinfunction "A0_3") (pintype "bidirectional"))
      (node (ref "COUNT2") (pin "8") (pinfunction "VDD_8") (pintype "bidirectional"))
      (node (ref "COUNT3") (pin "3") (pinfunction "A0_3") (pintype "bidirectional"))
      (node (ref "COUNT3") (pin "8") (pinfunction "VDD_8") (pintype "bidirectional"))
      (node (ref "COUNT4") (pin "8") (pinfunction "VDD_8") (pintype "bidirectional"))
      (node (ref "COUNT5") (pin "8") (pinfunction "VDD_8") (pintype "bidirectional"))
      (node (ref "COUNT6") (pin "8") (pinfunction "VDD_8") (pintype "bidirectional"))
      (node (ref "COUNT7") (pin "8") (pinfunction "VDD_8") (pintype "bidirectional"))
      (node (ref "DAC0") (pin "12") (pinfunction "VDD_12") (pintype "bidirectional"))
      (node (ref "DAC0") (pin "13") (pinfunction "REF3_13") (pintype "bidirectional"))
      (node (ref "DAC0") (pin "14") (pinfunction "REF2_14") (pintype "bidirectional"))
      (node (ref "DAC0") (pin "3") (pinfunction "REF1_3") (pintype "bidirectional"))
      (node (ref "DAC0") (pin "4") (pinfunction "REF0_4") (pintype "bidirectional"))
      (node (ref "DAC1") (pin "12") (pinfunction "VDD_12") (pintype "bidirectional"))
      (node (ref "DAC1") (pin "13") (pinfunction "REF3_13") (pintype "bidirectional"))
      (node (ref "DAC1") (pin "14") (pinfunction "REF2_14") (pintype "bidirectional"))
      (node (ref "DAC1") (pin "3") (pinfunction "REF1_3") (pintype "bidirectional"))
      (node (ref "DAC1") (pin "4") (pinfunction "REF0_4") (pintype "bidirectional"))
      (node (ref "DAC1") (pin "9") (pinfunction "AD0_9") (pintype "bidirectional"))
      (node (ref "L2") (pin "2") (pinfunction "2_2") (pintype "passive"))
      (node (ref "MULT0") (pin "16") (pinfunction "VDD_16") (pintype "bidirectional"))
      (node (ref "POW0") (pin "4") (pinfunction "SHDN_4") (pintype "bidirectional"))
      (node (ref "POW0") (pin "5") (pinfunction "VCC_5") (pintype "bidirectional"))
      (node (ref "POW1") (pin "1") (pinfunction "VIN_1") (pintype "bidirectional"))
      (node (ref "POWER") (pin "1") (pinfunction "1_1") (pintype "passive"))
      (node (ref "R1") (pin "1") (pinfunction "1_1") (pintype "passive"))
      (node (ref "RTD0") (pin "8") (pinfunction "VDD_8") (pintype "bidirectional"))
      (node (ref "RTD2") (pin "3") (pinfunction "3_3") (pintype "passive"))
      (node (ref "RTD2") (pin "4") (pinfunction "4_4") (pintype "passive"))
    )
    (net (code "2") (name "+12V") (class "Default")
      (node (ref "POW1") (pin "6") (pinfunction "+VO_6") (pintype "bidirectional"))
      (node (ref "PREAMP") (pin "6") (pinfunction "+V_6") (pintype "bidirectional"))
      (node (ref "SHAPE") (pin "5") (pinfunction "+V_5") (pintype "bidirectional"))
    )
    (net (code "3") (name "-12V") (class "Default")
      (node (ref "POW1") (pin "4") (pinfunction "-VO_4") (pintype "bidirectional"))
      (node (ref "PREAMP") (pin "5") (pinfunction "-V_5") (pintype "bidirectional"))
      (node (ref "SHAPE") (pin "4") (pinfunction "-V_4") (pintype "bidirectional"))
    )
    (net (code "4") (name "/AND0") (class "Default")
      (node (ref "COMP2") (pin "3") (pinfunction "INA+_3") (pintype "bidirectional"))
      (node (ref "R3") (pin "1") (pinfunction "1_1") (pintype "passive"))
      (node (ref "R4") (pin "1") (pinfunction "1_1") (pintype "passive"))
    )
    (net (code "5") (name "/AND1") (class "Default")
      (node (ref "COMP2") (pin "5") (pinfunction "INB+_5") (pintype "bidirectional"))
      (node (ref "R5") (pin "2") (pinfunction "2_2") (pintype "passive"))
      (node (ref "R6") (pin "2") (pinfunction "2_2") (pintype "passive"))
    )
    (net (code "6") (name "/AND2") (class "Default")
      (node (ref "COMP2") (pin "10") (pinfunction "INC+_10") (pintype "bidirectional"))
      (node (ref "R2") (pin "1") (pinfunction "1_1") (pintype "passive"))
      (node (ref "R7") (pin "1") (pinfunction "1_1") (pintype "passive"))
    )
    (net (code "7") (name "/AND3") (class "Default")
      (node (ref "COMP2") (pin "12") (pinfunction "IND+_12") (pintype "bidirectional"))
      (node (ref "R14") (pin "2") (pinfunction "2_2") (pintype "passive"))
      (node (ref "R8") (pin "2") (pinfunction "2_2") (pintype "passive"))
    )
    (net (code "8") (name "/AND4") (class "Default")
      (node (ref "COMP5") (pin "3") (pinfunction "INA+_3") (pintype "bidirectional"))
      (node (ref "R10") (pin "1") (pinfunction "1_1") (pintype "passive"))
      (node (ref "R17") (pin "1") (pinfunction "1_1") (pintype "passive"))
    )
    (net (code "9") (name "/AND5") (class "Default")
      (node (ref "COMP5") (pin "5") (pinfunction "INB+_5") (pintype "bidirectional"))
      (node (ref "R15") (pin "2") (pinfunction "2_2") (pintype "passive"))
      (node (ref "R16") (pin "2") (pinfunction "2_2") (pintype "passive"))
    )
    (net (code "10") (name "/AND6") (class "Default")
      (node (ref "COMP5") (pin "12") (pinfunction "IND+_12") (pintype "bidirectional"))
      (node (ref "R18") (pin "1") (pinfunction "1_1") (pintype "passive"))
      (node (ref "R19") (pin "1") (pinfunction "1_1") (pintype "passive"))
    )
    (net (code "11") (name "/AND7") (class "Default")
      (node (ref "COMP5") (pin "10") (pinfunction "INC+_10") (pintype "bidirectional"))
      (node (ref "R20") (pin "2") (pinfunction "2_2") (pintype "passive"))
      (node (ref "R21") (pin "2") (pinfunction "2_2") (pintype "passive"))
    )
    (net (code "12") (name "/BIN0") (class "Default")
      (node (ref "COMP2") (pin "1") (pinfunction "OUTA_1") (pintype "bidirectional"))
      (node (ref "COUNT0") (pin "1") (pinfunction "OSCI_1") (pintype "bidirectional"))
    )
    (net (code "13") (name "/BIN1") (class "Default")
      (node (ref "COMP2") (pin "7") (pinfunction "OUTB_7") (pintype "bidirectional"))
      (node (ref "COUNT1") (pin "1") (pinfunction "OSCI_1") (pintype "bidirectional"))
    )
    (net (code "14") (name "/BIN2") (class "Default")
      (node (ref "COMP2") (pin "8") (pinfunction "OUTC_8") (pintype "bidirectional"))
      (node (ref "COUNT2") (pin "1") (pinfunction "OSCI_1") (pintype "bidirectional"))
    )
    (net (code "15") (name "/BIN3") (class "Default")
      (node (ref "COMP2") (pin "14") (pinfunction "OUTD_14") (pintype "bidirectional"))
      (node (ref "COUNT3") (pin "1") (pinfunction "OSCI_1") (pintype "bidirectional"))
    )
    (net (code "16") (name "/BIN4") (class "Default")
      (node (ref "COMP5") (pin "1") (pinfunction "OUTA_1") (pintype "bidirectional"))
      (node (ref "COUNT4") (pin "1") (pinfunction "OSCI_1") (pintype "bidirectional"))
    )
    (net (code "17") (name "/BIN5") (class "Default")
      (node (ref "COMP5") (pin "7") (pinfunction "OUTB_7") (pintype "bidirectional"))
      (node (ref "COUNT5") (pin "1") (pinfunction "OSCI_1") (pintype "bidirectional"))
    )
    (net (code "18") (name "/BIN6") (class "Default")
      (node (ref "COMP5") (pin "14") (pinfunction "OUTD_14") (pintype "bidirectional"))
      (node (ref "COUNT6") (pin "1") (pinfunction "OSCI_1") (pintype "bidirectional"))
    )
    (net (code "19") (name "/BIN7") (class "Default")
      (node (ref "COMP5") (pin "8") (pinfunction "OUTC_8") (pintype "bidirectional"))
      (node (ref "COUNT7") (pin "1") (pinfunction "OSCI_1") (pintype "bidirectional"))
    )
    (net (code "20") (name "/COMPIN") (class "Default")
      (node (ref "AMP") (pin "1") (pinfunction "1_1") (pintype "passive"))
      (node (ref "COMP0") (pin "10") (pinfunction "INC+_10") (pintype "bidirectional"))
      (node (ref "COMP0") (pin "13") (pinfunction "IND-_13") (pintype "bidirectional"))
      (node (ref "COMP0") (pin "3") (pinfunction "INA+_3") (pintype "bidirectional"))
      (node (ref "COMP0") (pin "6") (pinfunction "INB-_6") (pintype "bidirectional"))
      (node (ref "COMP1") (pin "10") (pinfunction "INC+_10") (pintype "bidirectional"))
      (node (ref "COMP1") (pin "13") (pinfunction "IND-_13") (pintype "bidirectional"))
      (node (ref "COMP1") (pin "3") (pinfunction "INA+_3") (pintype "bidirectional"))
      (node (ref "COMP1") (pin "6") (pinfunction "INB-_6") (pintype "bidirectional"))
      (node (ref "COMP3") (pin "10") (pinfunction "INC+_10") (pintype "bidirectional"))
      (node (ref "COMP3") (pin "13") (pinfunction "IND-_13") (pintype "bidirectional"))
      (node (ref "COMP3") (pin "3") (pinfunction "INA+_3") (pintype "bidirectional"))
      (node (ref "COMP3") (pin "6") (pinfunction "INB-_6") (pintype "bidirectional"))
      (node (ref "COMP4") (pin "10") (pinfunction "INC+_10") (pintype "bidirectional"))
      (node (ref "COMP4") (pin "13") (pinfunction "IND-_13") (pintype "bidirectional"))
      (node (ref "COMP4") (pin "3") (pinfunction "INA+_3") (pintype "bidirectional"))
      (node (ref "COMP4") (pin "6") (pinfunction "INB-_6") (pintype "bidirectional"))
    )
    (net (code "21") (name "/GND2") (class "Default")
      (node (ref "CONN") (pin "3") (pinfunction "3_3") (pintype "passive"))
      (node (ref "R25") (pin "2") (pinfunction "2_2") (pintype "passive"))
    )
    (net (code "22") (name "/LEVEL0") (class "Default")
      (node (ref "COMP0") (pin "2") (pinfunction "INA-_2") (pintype "bidirectional"))
      (node (ref "DAC0") (pin "2") (pinfunction "OUT0_2") (pintype "bidirectional"))
      (node (ref "LEVELS") (pin "1") (pinfunction "1_1") (pintype "passive"))
    )
    (net (code "23") (name "/LEVEL1") (class "Default")
      (node (ref "COMP0") (pin "5") (pinfunction "INB+_5") (pintype "bidirectional"))
      (node (ref "COMP0") (pin "9") (pinfunction "INC-_9") (pintype "bidirectional"))
      (node (ref "DAC0") (pin "1") (pinfunction "OUT1_1") (pintype "bidirectional"))
      (node (ref "LEVELS") (pin "2") (pinfunction "2_2") (pintype "passive"))
    )
    (net (code "24") (name "/LEVEL2") (class "Default")
      (node (ref "COMP0") (pin "12") (pinfunction "IND+_12") (pintype "bidirectional"))
      (node (ref "COMP1") (pin "2") (pinfunction "INA-_2") (pintype "bidirectional"))
      (node (ref "DAC0") (pin "16") (pinfunction "OUT2_16") (pintype "bidirectional"))
      (node (ref "LEVELS") (pin "3") (pinfunction "3_3") (pintype "passive"))
    )
    (net (code "25") (name "/LEVEL3") (class "Default")
      (node (ref "COMP1") (pin "5") (pinfunction "INB+_5") (pintype "bidirectional"))
      (node (ref "COMP1") (pin "9") (pinfunction "INC-_9") (pintype "bidirectional"))
      (node (ref "DAC0") (pin "15") (pinfunction "OUT3_15") (pintype "bidirectional"))
      (node (ref "LEVELS") (pin "4") (pinfunction "4_4") (pintype "passive"))
    )
    (net (code "26") (name "/LEVEL4") (class "Default")
      (node (ref "COMP1") (pin "12") (pinfunction "IND+_12") (pintype "bidirectional"))
      (node (ref "COMP3") (pin "2") (pinfunction "INA-_2") (pintype "bidirectional"))
      (node (ref "DAC1") (pin "2") (pinfunction "OUT0_2") (pintype "bidirectional"))
      (node (ref "LEVELS") (pin "5") (pinfunction "5_5") (pintype "passive"))
    )
    (net (code "27") (name "/LEVEL5") (class "Default")
      (node (ref "COMP3") (pin "5") (pinfunction "INB+_5") (pintype "bidirectional"))
      (node (ref "COMP3") (pin "9") (pinfunction "INC-_9") (pintype "bidirectional"))
      (node (ref "DAC1") (pin "1") (pinfunction "OUT1_1") (pintype "bidirectional"))
      (node (ref "LEVELS") (pin "6") (pinfunction "6_6") (pintype "passive"))
    )
    (net (code "28") (name "/LEVEL6") (class "Default")
      (node (ref "COMP3") (pin "12") (pinfunction "IND+_12") (pintype "bidirectional"))
      (node (ref "COMP4") (pin "2") (pinfunction "INA-_2") (pintype "bidirectional"))
      (node (ref "DAC1") (pin "16") (pinfunction "OUT2_16") (pintype "bidirectional"))
      (node (ref "LEVELS") (pin "7") (pinfunction "7_7") (pintype "passive"))
    )
    (net (code "29") (name "/LEVEL7") (class "Default")
      (node (ref "COMP4") (pin "5") (pinfunction "INB+_5") (pintype "bidirectional"))
      (node (ref "COMP4") (pin "9") (pinfunction "INC-_9") (pintype "bidirectional"))
      (node (ref "DAC1") (pin "15") (pinfunction "OUT3_15") (pintype "bidirectional"))
      (node (ref "LEVELS") (pin "8") (pinfunction "8_8") (pintype "passive"))
    )
    (net (code "30") (name "/RESET1") (class "Default")
      (node (ref "MULT0") (pin "3") (pinfunction "RESET_3") (pintype "bidirectional"))
      (node (ref "RESET") (pin "1") (pinfunction "1_1") (pintype "passive"))
    )
    (net (code "31") (name "/RESET2") (class "Default")
      (node (ref "RESET") (pin "2") (pinfunction "2_2") (pintype "passive"))
    )
    (net (code "32") (name "/SC0") (class "Default")
      (node (ref "COUNT0") (pin "6") (pinfunction "SCL_6") (pintype "bidirectional"))
      (node (ref "COUNT4") (pin "6") (pinfunction "SCL_6") (pintype "bidirectional"))
      (node (ref "MULT0") (pin "5") (pinfunction "SC0_5") (pintype "bidirectional"))
    )
    (net (code "33") (name "/SC1") (class "Default")
      (node (ref "COUNT1") (pin "6") (pinfunction "SCL_6") (pintype "bidirectional"))
      (node (ref "COUNT5") (pin "6") (pinfunction "SCL_6") (pintype "bidirectional"))
      (node (ref "MULT0") (pin "7") (pinfunction "SC1_7") (pintype "bidirectional"))
    )
    (net (code "34") (name "/SC2") (class "Default")
      (node (ref "COUNT2") (pin "6") (pinfunction "SCL_6") (pintype "bidirectional"))
      (node (ref "COUNT6") (pin "6") (pinfunction "SCL_6") (pintype "bidirectional"))
      (node (ref "MULT0") (pin "10") (pinfunction "SC2_10") (pintype "bidirectional"))
    )
    (net (code "35") (name "/SC3") (class "Default")
      (node (ref "COUNT3") (pin "6") (pinfunction "SCL_6") (pintype "bidirectional"))
      (node (ref "COUNT7") (pin "6") (pinfunction "SCL_6") (pintype "bidirectional"))
      (node (ref "MULT0") (pin "12") (pinfunction "SC3_12") (pintype "bidirectional"))
    )
    (net (code "36") (name "/SCL") (class "Default")
      (node (ref "DAC0") (pin "7") (pinfunction "SCL_7") (pintype "bidirectional"))
      (node (ref "DAC1") (pin "7") (pinfunction "SCL_7") (pintype "bidirectional"))
      (node (ref "I2C") (pin "1") (pinfunction "1_1") (pintype "passive"))
      (node (ref "MULT0") (pin "14") (pinfunction "SCL_14") (pintype "bidirectional"))
      (node (ref "RTD0") (pin "2") (pinfunction "SCL_2") (pintype "bidirectional"))
      (node (ref "RTD1") (pin "2") (pinfunction "2_2") (pintype "passive"))
    )
    (net (code "37") (name "/SD0") (class "Default")
      (node (ref "COUNT0") (pin "5") (pinfunction "SDA_5") (pintype "bidirectional"))
      (node (ref "COUNT4") (pin "5") (pinfunction "SDA_5") (pintype "bidirectional"))
      (node (ref "MULT0") (pin "4") (pinfunction "SD0_4") (pintype "bidirectional"))
    )
    (net (code "38") (name "/SD1") (class "Default")
      (node (ref "COUNT1") (pin "5") (pinfunction "SDA_5") (pintype "bidirectional"))
      (node (ref "COUNT5") (pin "5") (pinfunction "SDA_5") (pintype "bidirectional"))
      (node (ref "MULT0") (pin "6") (pinfunction "SD1_6") (pintype "bidirectional"))
    )
    (net (code "39") (name "/SD2") (class "Default")
      (node (ref "COUNT2") (pin "5") (pinfunction "SDA_5") (pintype "bidirectional"))
      (node (ref "COUNT6") (pin "5") (pinfunction "SDA_5") (pintype "bidirectional"))
      (node (ref "MULT0") (pin "9") (pinfunction "SD2_9") (pintype "bidirectional"))
    )
    (net (code "40") (name "/SD3") (class "Default")
      (node (ref "COUNT3") (pin "5") (pinfunction "SDA_5") (pintype "bidirectional"))
      (node (ref "COUNT7") (pin "5") (pinfunction "SDA_5") (pintype "bidirectional"))
      (node (ref "MULT0") (pin "11") (pinfunction "SD3_11") (pintype "bidirectional"))
    )
    (net (code "41") (name "/SDA") (class "Default")
      (node (ref "DAC0") (pin "8") (pinfunction "SDA_8") (pintype "bidirectional"))
      (node (ref "DAC1") (pin "8") (pinfunction "SDA_8") (pintype "bidirectional"))
      (node (ref "I2C") (pin "2") (pinfunction "2_2") (pintype "passive"))
      (node (ref "MULT0") (pin "15") (pinfunction "SDA_15") (pintype "bidirectional"))
      (node (ref "RTD0") (pin "1") (pinfunction "SDA_1") (pintype "bidirectional"))
      (node (ref "RTD1") (pin "1") (pinfunction "1_1") (pintype "passive"))
    )
    (net (code "42") (name "/SHAPEIN") (class "Default")
      (node (ref "CONN") (pin "2") (pinfunction "2_2") (pintype "passive"))
      (node (ref "PREAMP") (pin "1") (pinfunction "IN_1") (pintype "bidirectional"))
    )
    (net (code "43") (name "/SHAPEOUT") (class "Default")
      (node (ref "AMP") (pin "2") (pinfunction "2_2") (pintype "passive"))
      (node (ref "SHAPE") (pin "8") (pinfunction "OUT_8") (pintype "bidirectional"))
    )
    (net (code "44") (name "30V") (class "Default")
      (node (ref "C16") (pin "2") (pinfunction "2_2") (pintype "passive"))
      (node (ref "CONN") (pin "1") (pinfunction "1_1") (pintype "passive"))
      (node (ref "D1") (pin "C") (pinfunction "C_C") (pintype "passive"))
      (node (ref "R22") (pin "2") (pinfunction "2_2") (pintype "passive"))
    )
    (net (code "45") (name "GND") (class "Default")
      (node (ref "C1") (pin "1") (pinfunction "1_1") (pintype "passive"))
      (node (ref "C10") (pin "1") (pinfunction "1_1") (pintype "passive"))
      (node (ref "C11") (pin "P") (pinfunction "P_P") (pintype "passive"))
      (node (ref "C12") (pin "P") (pinfunction "P_P") (pintype "passive"))
      (node (ref "C13") (pin "1") (pinfunction "1_1") (pintype "passive"))
      (node (ref "C14") (pin "1") (pinfunction "1_1") (pintype "passive"))
      (node (ref "C15") (pin "1") (pinfunction "1_1") (pintype "passive"))
      (node (ref "C16") (pin "1") (pinfunction "1_1") (pintype "passive"))
      (node (ref "C17") (pin "1") (pinfunction "1_1") (pintype "passive"))
      (node (ref "C18") (pin "P") (pinfunction "P_P") (pintype "passive"))
      (node (ref "C19") (pin "P") (pinfunction "P_P") (pintype "passive"))
      (node (ref "C2") (pin "P") (pinfunction "P_P") (pintype "passive"))
      (node (ref "C20") (pin "P") (pinfunction "P_P") (pintype "passive"))
      (node (ref "C23") (pin "1") (pinfunction "1_1") (pintype "passive"))
      (node (ref "C24") (pin "P") (pinfunction "P_P") (pintype "passive"))
      (node (ref "C25") (pin "1") (pinfunction "1_1") (pintype "passive"))
      (node (ref "C26") (pin "P") (pinfunction "P_P") (pintype "passive"))
      (node (ref "C27") (pin "1") (pinfunction "1_1") (pintype "passive"))
      (node (ref "C28") (pin "P") (pinfunction "P_P") (pintype "passive"))
      (node (ref "C29") (pin "1") (pinfunction "1_1") (pintype "passive"))
      (node (ref "C3") (pin "1") (pinfunction "1_1") (pintype "passive"))
      (node (ref "C30") (pin "P") (pinfunction "P_P") (pintype "passive"))
      (node (ref "C31") (pin "1") (pinfunction "1_1") (pintype "passive"))
      (node (ref "C32") (pin "P") (pinfunction "P_P") (pintype "passive"))
      (node (ref "C33") (pin "1") (pinfunction "1_1") (pintype "passive"))
      (node (ref "C34") (pin "P") (pinfunction "P_P") (pintype "passive"))
      (node (ref "C35") (pin "1") (pinfunction "1_1") (pintype "passive"))
      (node (ref "C36") (pin "P") (pinfunction "P_P") (pintype "passive"))
      (node (ref "C37") (pin "1") (pinfunction "1_1") (pintype "passive"))
      (node (ref "C38") (pin "1") (pinfunction "1_1") (pintype "passive"))
      (node (ref "C39") (pin "1") (pinfunction "1_1") (pintype "passive"))
      (node (ref "C4") (pin "P") (pinfunction "P_P") (pintype "passive"))
      (node (ref "C40") (pin "P") (pinfunction "P_P") (pintype "passive"))
      (node (ref "C41") (pin "P") (pinfunction "P_P") (pintype "passive"))
      (node (ref "C42") (pin "P") (pinfunction "P_P") (pintype "passive"))
      (node (ref "C5") (pin "1") (pinfunction "1_1") (pintype "passive"))
      (node (ref "C6") (pin "P") (pinfunction "P_P") (pintype "passive"))
      (node (ref "C7") (pin "1") (pinfunction "1_1") (pintype "passive"))
      (node (ref "C8") (pin "P") (pinfunction "P_P") (pintype "passive"))
      (node (ref "C9") (pin "1") (pinfunction "1_1") (pintype "passive"))
      (node (ref "COMP0") (pin "11") (pinfunction "GND_11") (pintype "bidirectional"))
      (node (ref "COMP1") (pin "11") (pinfunction "GND_11") (pintype "bidirectional"))
      (node (ref "COMP2") (pin "11") (pinfunction "GND_11") (pintype "bidirectional"))
      (node (ref "COMP3") (pin "11") (pinfunction "GND_11") (pintype "bidirectional"))
      (node (ref "COMP4") (pin "11") (pinfunction "GND_11") (pintype "bidirectional"))
      (node (ref "COMP5") (pin "11") (pinfunction "GND_11") (pintype "bidirectional"))
      (node (ref "COUNT0") (pin "4") (pinfunction "VSS_4") (pintype "bidirectional"))
      (node (ref "COUNT1") (pin "4") (pinfunction "VSS_4") (pintype "bidirectional"))
      (node (ref "COUNT2") (pin "4") (pinfunction "VSS_4") (pintype "bidirectional"))
      (node (ref "COUNT3") (pin "4") (pinfunction "VSS_4") (pintype "bidirectional"))
      (node (ref "COUNT4") (pin "3") (pinfunction "A0_3") (pintype "bidirectional"))
      (node (ref "COUNT4") (pin "4") (pinfunction "VSS_4") (pintype "bidirectional"))
      (node (ref "COUNT5") (pin "3") (pinfunction "A0_3") (pintype "bidirectional"))
      (node (ref "COUNT5") (pin "4") (pinfunction "VSS_4") (pintype "bidirectional"))
      (node (ref "COUNT6") (pin "3") (pinfunction "A0_3") (pintype "bidirectional"))
      (node (ref "COUNT6") (pin "4") (pinfunction "VSS_4") (pintype "bidirectional"))
      (node (ref "COUNT7") (pin "3") (pinfunction "A0_3") (pintype "bidirectional"))
      (node (ref "COUNT7") (pin "4") (pinfunction "VSS_4") (pintype "bidirectional"))
      (node (ref "DAC0") (pin "10") (pinfunction "AD1_10") (pintype "bidirectional"))
      (node (ref "DAC0") (pin "11") (pinfunction "AD2_11") (pintype "bidirectional"))
      (node (ref "DAC0") (pin "5") (pinfunction "AGND_5") (pintype "bidirectional"))
      (node (ref "DAC0") (pin "6") (pinfunction "DGND_6") (pintype "bidirectional"))
      (node (ref "DAC0") (pin "9") (pinfunction "AD0_9") (pintype "bidirectional"))
      (node (ref "DAC1") (pin "10") (pinfunction "AD1_10") (pintype "bidirectional"))
      (node (ref "DAC1") (pin "11") (pinfunction "AD2_11") (pintype "bidirectional"))
      (node (ref "DAC1") (pin "5") (pinfunction "AGND_5") (pintype "bidirectional"))
      (node (ref "DAC1") (pin "6") (pinfunction "DGND_6") (pintype "bidirectional"))
      (node (ref "MULT0") (pin "1") (pinfunction "A0_1") (pintype "bidirectional"))
      (node (ref "MULT0") (pin "13") (pinfunction "A2_13") (pintype "bidirectional"))
      (node (ref "MULT0") (pin "2") (pinfunction "A1_2") (pintype "bidirectional"))
      (node (ref "MULT0") (pin "8") (pinfunction "VSS_8") (pintype "bidirectional"))
      (node (ref "POW0") (pin "1") (pinfunction "PGND_1") (pintype "bidirectional"))
      (node (ref "POW0") (pin "2") (pinfunction "GND_2") (pintype "bidirectional"))
      (node (ref "POW1") (pin "2") (pinfunction "GND_2") (pintype "bidirectional"))
      (node (ref "POW1") (pin "5") (pinfunction "0V_5") (pintype "bidirectional"))
      (node (ref "POWER") (pin "2") (pinfunction "2_2") (pintype "passive"))
      (node (ref "PREAMP") (pin "2") (pinfunction "GND1_2") (pintype "bidirectional"))
      (node (ref "PREAMP") (pin "4") (pinfunction "GND2_4") (pintype "bidirectional"))
      (node (ref "PREAMP") (pin "7") (pinfunction "GND3_7") (pintype "bidirectional"))
      (node (ref "R23") (pin "1") (pinfunction "1_1") (pintype "passive"))
      (node (ref "R25") (pin "1") (pinfunction "1_1") (pintype "passive"))
      (node (ref "R9") (pin "2") (pinfunction "2_2") (pintype "passive"))
      (node (ref "RTD0") (pin "4") (pinfunction "GND_4") (pintype "bidirectional"))
      (node (ref "RTD0") (pin "5") (pinfunction "AD2_5") (pintype "bidirectional"))
      (node (ref "RTD0") (pin "6") (pinfunction "AD1_6") (pintype "bidirectional"))
      (node (ref "RTD0") (pin "7") (pinfunction "AD0_7") (pintype "bidirectional"))
      (node (ref "RTD1") (pin "4") (pinfunction "4_4") (pintype "passive"))
      (node (ref "RTD2") (pin "2") (pinfunction "2_2") (pintype "passive"))
      (node (ref "SHAPE") (pin "3") (pinfunction "GND1_3") (pintype "bidirectional"))
      (node (ref "SHAPE") (pin "6") (pinfunction "GND2_6") (pintype "bidirectional"))
      (node (ref "SHAPE") (pin "7") (pinfunction "GND3_7") (pintype "bidirectional"))
    )
    (net (code "46") (name "Net-(COMP0-OUTA)") (class "Default")
      (node (ref "COMP0") (pin "1") (pinfunction "OUTA_1") (pintype "bidirectional"))
      (node (ref "R3") (pin "2") (pinfunction "2_2") (pintype "passive"))
    )
    (net (code "47") (name "Net-(COMP0-OUTB)") (class "Default")
      (node (ref "COMP0") (pin "7") (pinfunction "OUTB_7") (pintype "bidirectional"))
      (node (ref "R4") (pin "2") (pinfunction "2_2") (pintype "passive"))
    )
    (net (code "48") (name "Net-(COMP0-OUTC)") (class "Default")
      (node (ref "COMP0") (pin "8") (pinfunction "OUTC_8") (pintype "bidirectional"))
      (node (ref "R6") (pin "1") (pinfunction "1_1") (pintype "passive"))
    )
    (net (code "49") (name "Net-(COMP0-OUTD)") (class "Default")
      (node (ref "COMP0") (pin "14") (pinfunction "OUTD_14") (pintype "bidirectional"))
      (node (ref "R5") (pin "1") (pinfunction "1_1") (pintype "passive"))
    )
    (net (code "50") (name "Net-(COMP1-OUTA)") (class "Default")
      (node (ref "COMP1") (pin "1") (pinfunction "OUTA_1") (pintype "bidirectional"))
      (node (ref "R2") (pin "2") (pinfunction "2_2") (pintype "passive"))
    )
    (net (code "51") (name "Net-(COMP1-OUTB)") (class "Default")
      (node (ref "COMP1") (pin "7") (pinfunction "OUTB_7") (pintype "bidirectional"))
      (node (ref "R7") (pin "2") (pinfunction "2_2") (pintype "passive"))
    )
    (net (code "52") (name "Net-(COMP1-OUTC)") (class "Default")
      (node (ref "COMP1") (pin "8") (pinfunction "OUTC_8") (pintype "bidirectional"))
      (node (ref "R14") (pin "1") (pinfunction "1_1") (pintype "passive"))
    )
    (net (code "53") (name "Net-(COMP1-OUTD)") (class "Default")
      (node (ref "COMP1") (pin "14") (pinfunction "OUTD_14") (pintype "bidirectional"))
      (node (ref "R8") (pin "1") (pinfunction "1_1") (pintype "passive"))
    )
    (net (code "54") (name "Net-(COMP2-INA-)") (class "Default")
      (node (ref "COMP2") (pin "13") (pinfunction "IND-_13") (pintype "bidirectional"))
      (node (ref "COMP2") (pin "2") (pinfunction "INA-_2") (pintype "bidirectional"))
      (node (ref "COMP2") (pin "6") (pinfunction "INB-_6") (pintype "bidirectional"))
      (node (ref "COMP2") (pin "9") (pinfunction "INC-_9") (pintype "bidirectional"))
      (node (ref "COMP5") (pin "13") (pinfunction "IND-_13") (pintype "bidirectional"))
      (node (ref "COMP5") (pin "2") (pinfunction "INA-_2") (pintype "bidirectional"))
      (node (ref "COMP5") (pin "6") (pinfunction "INB-_6") (pintype "bidirectional"))
      (node (ref "COMP5") (pin "9") (pinfunction "INC-_9") (pintype "bidirectional"))
      (node (ref "R1") (pin "2") (pinfunction "2_2") (pintype "passive"))
      (node (ref "R9") (pin "1") (pinfunction "1_1") (pintype "passive"))
    )
    (net (code "55") (name "Net-(COMP3-OUTA)") (class "Default")
      (node (ref "COMP3") (pin "1") (pinfunction "OUTA_1") (pintype "bidirectional"))
      (node (ref "R10") (pin "2") (pinfunction "2_2") (pintype "passive"))
    )
    (net (code "56") (name "Net-(COMP3-OUTB)") (class "Default")
      (node (ref "COMP3") (pin "7") (pinfunction "OUTB_7") (pintype "bidirectional"))
      (node (ref "R17") (pin "2") (pinfunction "2_2") (pintype "passive"))
    )
    (net (code "57") (name "Net-(COMP3-OUTC)") (class "Default")
      (node (ref "COMP3") (pin "8") (pinfunction "OUTC_8") (pintype "bidirectional"))
      (node (ref "R16") (pin "1") (pinfunction "1_1") (pintype "passive"))
    )
    (net (code "58") (name "Net-(COMP3-OUTD)") (class "Default")
      (node (ref "COMP3") (pin "14") (pinfunction "OUTD_14") (pintype "bidirectional"))
      (node (ref "R15") (pin "1") (pinfunction "1_1") (pintype "passive"))
    )
    (net (code "59") (name "Net-(COMP4-OUTA)") (class "Default")
      (node (ref "COMP4") (pin "1") (pinfunction "OUTA_1") (pintype "bidirectional"))
      (node (ref "R18") (pin "2") (pinfunction "2_2") (pintype "passive"))
    )
    (net (code "60") (name "Net-(COMP4-OUTB)") (class "Default")
      (node (ref "COMP4") (pin "7") (pinfunction "OUTB_7") (pintype "bidirectional"))
      (node (ref "R19") (pin "2") (pinfunction "2_2") (pintype "passive"))
    )
    (net (code "61") (name "Net-(COMP4-OUTC)") (class "Default")
      (node (ref "COMP4") (pin "8") (pinfunction "OUTC_8") (pintype "bidirectional"))
      (node (ref "R20") (pin "1") (pinfunction "1_1") (pintype "passive"))
    )
    (net (code "62") (name "Net-(COMP4-OUTD)") (class "Default")
      (node (ref "COMP4") (pin "14") (pinfunction "OUTD_14") (pintype "bidirectional"))
      (node (ref "R21") (pin "1") (pinfunction "1_1") (pintype "passive"))
    )
    (net (code "63") (name "Net-(POW0-FB)") (class "Default")
      (node (ref "POW0") (pin "3") (pinfunction "FB_3") (pintype "bidirectional"))
      (node (ref "R22") (pin "1") (pinfunction "1_1") (pintype "passive"))
      (node (ref "R23") (pin "2") (pinfunction "2_2") (pintype "passive"))
    )
    (net (code "64") (name "Net-(POW0-LX)") (class "Default")
      (node (ref "D1") (pin "A") (pinfunction "A_A") (pintype "passive"))
      (node (ref "L2") (pin "1") (pinfunction "1_1") (pintype "passive"))
      (node (ref "POW0") (pin "6") (pinfunction "LX_6") (pintype "bidirectional"))
    )
    (net (code "65") (name "Net-(PREAMP-OUT)") (class "Default")
      (node (ref "PREAMP") (pin "8") (pinfunction "OUT_8") (pintype "bidirectional"))
      (node (ref "R11") (pin "1") (pinfunction "1_1") (pintype "passive"))
      (node (ref "SHAPE") (pin "1") (pinfunction "IN_1") (pintype "bidirectional"))
    )
    (net (code "66") (name "Net-(SHAPE-P{slash}Z)") (class "Default")
      (node (ref "R11") (pin "2") (pinfunction "2_2") (pintype "passive"))
      (node (ref "SHAPE") (pin "2") (pinfunction "P/Z_2") (pintype "bidirectional"))
    )
    (net (code "67") (name "unconnected-(COUNT0-INT-Pad7)") (class "Default")
      (node (ref "COUNT0") (pin "7") (pinfunction "INT_7") (pintype "bidirectional"))
    )
    (net (code "68") (name "unconnected-(COUNT0-OSCO-Pad2)") (class "Default")
      (node (ref "COUNT0") (pin "2") (pinfunction "OSCO_2") (pintype "bidirectional"))
    )
    (net (code "69") (name "unconnected-(COUNT1-INT-Pad7)") (class "Default")
      (node (ref "COUNT1") (pin "7") (pinfunction "INT_7") (pintype "bidirectional"))
    )
    (net (code "70") (name "unconnected-(COUNT1-OSCO-Pad2)") (class "Default")
      (node (ref "COUNT1") (pin "2") (pinfunction "OSCO_2") (pintype "bidirectional"))
    )
    (net (code "71") (name "unconnected-(COUNT2-INT-Pad7)") (class "Default")
      (node (ref "COUNT2") (pin "7") (pinfunction "INT_7") (pintype "bidirectional"))
    )
    (net (code "72") (name "unconnected-(COUNT2-OSCO-Pad2)") (class "Default")
      (node (ref "COUNT2") (pin "2") (pinfunction "OSCO_2") (pintype "bidirectional"))
    )
    (net (code "73") (name "unconnected-(COUNT3-INT-Pad7)") (class "Default")
      (node (ref "COUNT3") (pin "7") (pinfunction "INT_7") (pintype "bidirectional"))
    )
    (net (code "74") (name "unconnected-(COUNT3-OSCO-Pad2)") (class "Default")
      (node (ref "COUNT3") (pin "2") (pinfunction "OSCO_2") (pintype "bidirectional"))
    )
    (net (code "75") (name "unconnected-(COUNT4-INT-Pad7)") (class "Default")
      (node (ref "COUNT4") (pin "7") (pinfunction "INT_7") (pintype "bidirectional"))
    )
    (net (code "76") (name "unconnected-(COUNT4-OSCO-Pad2)") (class "Default")
      (node (ref "COUNT4") (pin "2") (pinfunction "OSCO_2") (pintype "bidirectional"))
    )
    (net (code "77") (name "unconnected-(COUNT5-INT-Pad7)") (class "Default")
      (node (ref "COUNT5") (pin "7") (pinfunction "INT_7") (pintype "bidirectional"))
    )
    (net (code "78") (name "unconnected-(COUNT5-OSCO-Pad2)") (class "Default")
      (node (ref "COUNT5") (pin "2") (pinfunction "OSCO_2") (pintype "bidirectional"))
    )
    (net (code "79") (name "unconnected-(COUNT6-INT-Pad7)") (class "Default")
      (node (ref "COUNT6") (pin "7") (pinfunction "INT_7") (pintype "bidirectional"))
    )
    (net (code "80") (name "unconnected-(COUNT6-OSCO-Pad2)") (class "Default")
      (node (ref "COUNT6") (pin "2") (pinfunction "OSCO_2") (pintype "bidirectional"))
    )
    (net (code "81") (name "unconnected-(COUNT7-INT-Pad7)") (class "Default")
      (node (ref "COUNT7") (pin "7") (pinfunction "INT_7") (pintype "bidirectional"))
    )
    (net (code "82") (name "unconnected-(COUNT7-OSCO-Pad2)") (class "Default")
      (node (ref "COUNT7") (pin "2") (pinfunction "OSCO_2") (pintype "bidirectional"))
    )
    (net (code "83") (name "unconnected-(PREAMP-NC-Pad3)") (class "Default")
      (node (ref "PREAMP") (pin "3") (pinfunction "NC_3") (pintype "bidirectional"))
    )
    (net (code "84") (name "unconnected-(RTD0-ALERT-Pad3)") (class "Default")
      (node (ref "RTD0") (pin "3") (pinfunction "ALERT_3") (pintype "bidirectional"))
    )
    (net (code "85") (name "unconnected-(RTD1-Pad3)") (class "Default")
      (node (ref "RTD1") (pin "3") (pinfunction "3_3") (pintype "passive"))
    )
    (net (code "86") (name "unconnected-(RTD2-Pad1)") (class "Default")
      (node (ref "RTD2") (pin "1") (pinfunction "1_1") (pintype "passive"))
    )
  )
)
